# LIGHT.net
KiCad netlist of a schematic drawn in Altium Designer
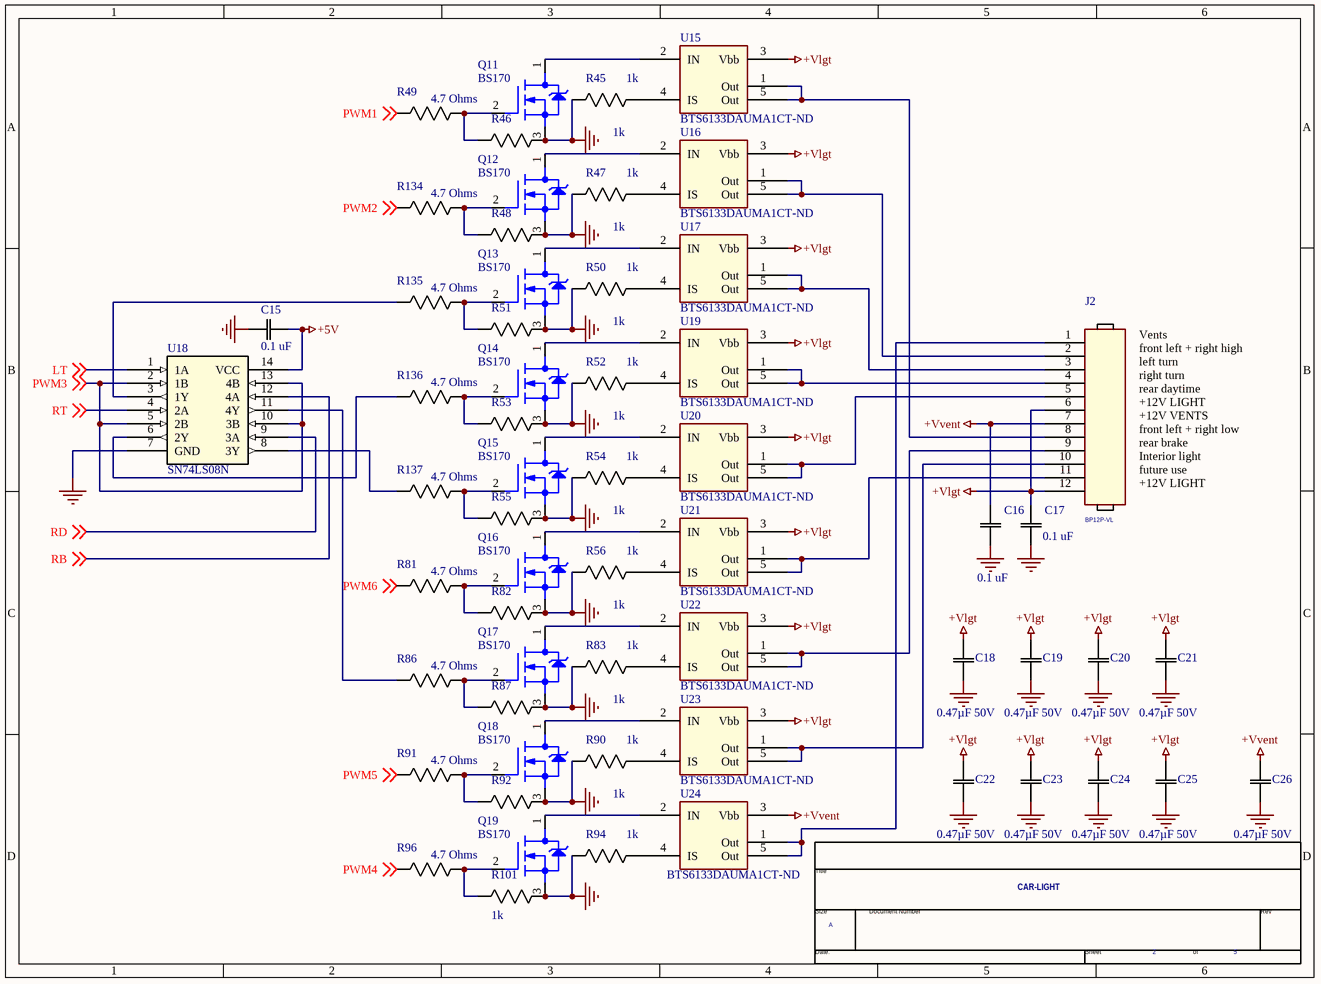
[diagram p0: LIGHT.SchDoc]

(export (version "E")
  (design (tool "Eeschema 10.0.6"))
  (components
    (comp (ref "C15")
      (value "0.1 uF")
      (footprint "SR20")
      (description "0.1µF ±10% 100V Ceramic Capacitor X7R Radial")
      (fields (field (name "MANUFACTURER_PART_NUMBER") "C320C104K1R5TA7301"))
      (libsource (lib "Discrete") (part "CAP RADIAL 2.54"))
    )
    (comp (ref "C16")
      (value "0.1 uF")
      (footprint "SR20")
      (description "0.1µF ±10% 100V Ceramic Capacitor X7R Radial")
      (fields (field (name "MANUFACTURER_PART_NUMBER") "C320C104K1R5TA7301"))
      (libsource (lib "Discrete") (part "CAP RADIAL 2.54"))
    )
    (comp (ref "C17")
      (value "0.1 uF")
      (footprint "SR20")
      (description "0.1µF ±10% 100V Ceramic Capacitor X7R Radial")
      (fields (field (name "MANUFACTURER_PART_NUMBER") "C320C104K1R5TA7301"))
      (libsource (lib "Discrete") (part "CAP RADIAL 2.54"))
    )
    (comp (ref "C18")
      (value "0.47µF 50V")
      (footprint "SR20")
      (description "CAP CER 0.47UF 50V X7R RADIAL")
      (fields (field (name "MANUFACTURER_PART_NUMBER") "C315C474K5R5TA7303"))
      (libsource (lib "Discrete") (part "CAP RADIAL 2.54"))
    )
    (comp (ref "C19")
      (value "0.47µF 50V")
      (footprint "SR20")
      (description "CAP CER 0.47UF 50V X7R RADIAL")
      (fields (field (name "MANUFACTURER_PART_NUMBER") "C315C474K5R5TA7303"))
      (libsource (lib "Discrete") (part "CAP RADIAL 2.54"))
    )
    (comp (ref "C20")
      (value "0.47µF 50V")
      (footprint "SR20")
      (description "CAP CER 0.47UF 50V X7R RADIAL")
      (fields (field (name "MANUFACTURER_PART_NUMBER") "C315C474K5R5TA7303"))
      (libsource (lib "Discrete") (part "CAP RADIAL 2.54"))
    )
    (comp (ref "C21")
      (value "0.47µF 50V")
      (footprint "SR20")
      (description "CAP CER 0.47UF 50V X7R RADIAL")
      (fields (field (name "MANUFACTURER_PART_NUMBER") "C315C474K5R5TA7303"))
      (libsource (lib "Discrete") (part "CAP RADIAL 2.54"))
    )
    (comp (ref "C22")
      (value "0.47µF 50V")
      (footprint "SR20")
      (description "CAP CER 0.47UF 50V X7R RADIAL")
      (fields (field (name "MANUFACTURER_PART_NUMBER") "C315C474K5R5TA7303"))
      (libsource (lib "Discrete") (part "CAP RADIAL 2.54"))
    )
    (comp (ref "C23")
      (value "0.47µF 50V")
      (footprint "SR20")
      (description "CAP CER 0.47UF 50V X7R RADIAL")
      (fields (field (name "MANUFACTURER_PART_NUMBER") "C315C474K5R5TA7303"))
      (libsource (lib "Discrete") (part "CAP RADIAL 2.54"))
    )
    (comp (ref "C24")
      (value "0.47µF 50V")
      (footprint "SR20")
      (description "CAP CER 0.47UF 50V X7R RADIAL")
      (fields (field (name "MANUFACTURER_PART_NUMBER") "C315C474K5R5TA7303"))
      (libsource (lib "Discrete") (part "CAP RADIAL 2.54"))
    )
    (comp (ref "C25")
      (value "0.47µF 50V")
      (footprint "SR20")
      (description "CAP CER 0.47UF 50V X7R RADIAL")
      (fields (field (name "MANUFACTURER_PART_NUMBER") "C315C474K5R5TA7303"))
      (libsource (lib "Discrete") (part "CAP RADIAL 2.54"))
    )
    (comp (ref "C26")
      (value "0.47µF 50V")
      (footprint "SR20")
      (description "CAP CER 0.47UF 50V X7R RADIAL")
      (fields (field (name "MANUFACTURER_PART_NUMBER") "C315C474K5R5TA7303"))
      (libsource (lib "Discrete") (part "CAP RADIAL 2.54"))
    )
    (comp (ref "J2")
      (value "BP12P-VL")
      (footprint "MOLEX_0874271202")
      (libsource (lib "*") (part "HEADER 12"))
    )
    (comp (ref "Q11")
      (value "BS170")
      (footprint "Discrete:TO-92")
      (description "MOSFET N-CH 60V 500MA TO-92")
      (fields (field (name "MANUFACTURER_PART_NUMBER") "ON Semiconductor"))
      (libsource (lib "Discrete") (part "BS170"))
    )
    (comp (ref "Q12")
      (value "BS170")
      (footprint "Discrete:TO-92")
      (description "MOSFET N-CH 60V 500MA TO-92")
      (fields (field (name "MANUFACTURER_PART_NUMBER") "ON Semiconductor"))
      (libsource (lib "Discrete") (part "BS170"))
    )
    (comp (ref "Q13")
      (value "BS170")
      (footprint "Discrete:TO-92")
      (description "MOSFET N-CH 60V 500MA TO-92")
      (fields (field (name "MANUFACTURER_PART_NUMBER") "ON Semiconductor"))
      (libsource (lib "Discrete") (part "BS170"))
    )
    (comp (ref "Q14")
      (value "BS170")
      (footprint "Discrete:TO-92")
      (description "MOSFET N-CH 60V 500MA TO-92")
      (fields (field (name "MANUFACTURER_PART_NUMBER") "ON Semiconductor"))
      (libsource (lib "Discrete") (part "BS170"))
    )
    (comp (ref "Q15")
      (value "BS170")
      (footprint "Discrete:TO-92")
      (description "MOSFET N-CH 60V 500MA TO-92")
      (fields (field (name "MANUFACTURER_PART_NUMBER") "ON Semiconductor"))
      (libsource (lib "Discrete") (part "BS170"))
    )
    (comp (ref "Q16")
      (value "BS170")
      (footprint "Discrete:TO-92")
      (description "MOSFET N-CH 60V 500MA TO-92")
      (fields (field (name "MANUFACTURER_PART_NUMBER") "ON Semiconductor"))
      (libsource (lib "Discrete") (part "BS170"))
    )
    (comp (ref "Q17")
      (value "BS170")
      (footprint "Discrete:TO-92")
      (description "MOSFET N-CH 60V 500MA TO-92")
      (fields (field (name "MANUFACTURER_PART_NUMBER") "ON Semiconductor"))
      (libsource (lib "Discrete") (part "BS170"))
    )
    (comp (ref "Q18")
      (value "BS170")
      (footprint "Discrete:TO-92")
      (description "MOSFET N-CH 60V 500MA TO-92")
      (fields (field (name "MANUFACTURER_PART_NUMBER") "ON Semiconductor"))
      (libsource (lib "Discrete") (part "BS170"))
    )
    (comp (ref "Q19")
      (value "BS170")
      (footprint "Discrete:TO-92")
      (description "MOSFET N-CH 60V 500MA TO-92")
      (fields (field (name "MANUFACTURER_PART_NUMBER") "ON Semiconductor"))
      (libsource (lib "Discrete") (part "BS170"))
    )
    (comp (ref "R45")
      (value "1k")
      (footprint "RES AXIAL 1/6W")
      (description "RES 1K OHM 1/6W 5% AXIAL")
      (fields (field (name "MANUFACTURER_PART_NUMBER") "CFR-12JB-52-1K"))
      (libsource (lib "Discrete") (part "Resistor Axial  1/6W"))
    )
    (comp (ref "R46")
      (value "1k")
      (footprint "RES AXIAL 1/6W")
      (description "RES 1K OHM 1/6W 5% AXIAL")
      (fields (field (name "MANUFACTURER_PART_NUMBER") "CFR-12JB-52-1K"))
      (libsource (lib "Discrete") (part "Resistor Axial  1/6W"))
    )
    (comp (ref "R47")
      (value "1k")
      (footprint "RES AXIAL 1/6W")
      (description "RES 1K OHM 1/6W 5% AXIAL")
      (fields (field (name "MANUFACTURER_PART_NUMBER") "CFR-12JB-52-1K"))
      (libsource (lib "Discrete") (part "Resistor Axial  1/6W"))
    )
    (comp (ref "R48")
      (value "1k")
      (footprint "RES AXIAL 1/6W")
      (description "RES 1K OHM 1/6W 5% AXIAL")
      (fields (field (name "MANUFACTURER_PART_NUMBER") "CFR-12JB-52-1K"))
      (libsource (lib "Discrete") (part "Resistor Axial  1/6W"))
    )
    (comp (ref "R49")
      (value "4.7 Ohms")
      (footprint "RES AXIAL 1/6W")
      (description "RES 4.7 OHM 1/6W 5% AXIAL")
      (fields (field (name "MANUFACTURER_PART_NUMBER") "CFR-12JB-52-4R7"))
      (libsource (lib "Discrete") (part "Resistor Axial  1/6W"))
    )
    (comp (ref "R50")
      (value "1k")
      (footprint "RES AXIAL 1/6W")
      (description "RES 1K OHM 1/6W 5% AXIAL")
      (fields (field (name "MANUFACTURER_PART_NUMBER") "CFR-12JB-52-1K"))
      (libsource (lib "Discrete") (part "Resistor Axial  1/6W"))
    )
    (comp (ref "R51")
      (value "1k")
      (footprint "RES AXIAL 1/6W")
      (description "RES 1K OHM 1/6W 5% AXIAL")
      (fields (field (name "MANUFACTURER_PART_NUMBER") "CFR-12JB-52-1K"))
      (libsource (lib "Discrete") (part "Resistor Axial  1/6W"))
    )
    (comp (ref "R52")
      (value "1k")
      (footprint "RES AXIAL 1/6W")
      (description "RES 1K OHM 1/6W 5% AXIAL")
      (fields (field (name "MANUFACTURER_PART_NUMBER") "CFR-12JB-52-1K"))
      (libsource (lib "Discrete") (part "Resistor Axial  1/6W"))
    )
    (comp (ref "R53")
      (value "1k")
      (footprint "RES AXIAL 1/6W")
      (description "RES 1K OHM 1/6W 5% AXIAL")
      (fields (field (name "MANUFACTURER_PART_NUMBER") "CFR-12JB-52-1K"))
      (libsource (lib "Discrete") (part "Resistor Axial  1/6W"))
    )
    (comp (ref "R54")
      (value "1k")
      (footprint "RES AXIAL 1/6W")
      (description "RES 1K OHM 1/6W 5% AXIAL")
      (fields (field (name "MANUFACTURER_PART_NUMBER") "CFR-12JB-52-1K"))
      (libsource (lib "Discrete") (part "Resistor Axial  1/6W"))
    )
    (comp (ref "R55")
      (value "1k")
      (footprint "RES AXIAL 1/6W")
      (description "RES 1K OHM 1/6W 5% AXIAL")
      (fields (field (name "MANUFACTURER_PART_NUMBER") "CFR-12JB-52-1K"))
      (libsource (lib "Discrete") (part "Resistor Axial  1/6W"))
    )
    (comp (ref "R56")
      (value "1k")
      (footprint "RES AXIAL 1/6W")
      (description "RES 1K OHM 1/6W 5% AXIAL")
      (fields (field (name "MANUFACTURER_PART_NUMBER") "CFR-12JB-52-1K"))
      (libsource (lib "Discrete") (part "Resistor Axial  1/6W"))
    )
    (comp (ref "R81")
      (value "4.7 Ohms")
      (footprint "RES AXIAL 1/6W")
      (description "RES 4.7 OHM 1/6W 5% AXIAL")
      (fields (field (name "MANUFACTURER_PART_NUMBER") "CFR-12JB-52-4R7"))
      (libsource (lib "Discrete") (part "Resistor Axial  1/6W"))
    )
    (comp (ref "R82")
      (value "1k")
      (footprint "RES AXIAL 1/6W")
      (description "RES 1K OHM 1/6W 5% AXIAL")
      (fields (field (name "MANUFACTURER_PART_NUMBER") "CFR-12JB-52-1K"))
      (libsource (lib "Discrete") (part "Resistor Axial  1/6W"))
    )
    (comp (ref "R83")
      (value "1k")
      (footprint "RES AXIAL 1/6W")
      (description "RES 1K OHM 1/6W 5% AXIAL")
      (fields (field (name "MANUFACTURER_PART_NUMBER") "CFR-12JB-52-1K"))
      (libsource (lib "Discrete") (part "Resistor Axial  1/6W"))
    )
    (comp (ref "R86")
      (value "4.7 Ohms")
      (footprint "RES AXIAL 1/6W")
      (description "RES 4.7 OHM 1/6W 5% AXIAL")
      (fields (field (name "MANUFACTURER_PART_NUMBER") "CFR-12JB-52-4R7"))
      (libsource (lib "Discrete") (part "Resistor Axial  1/6W"))
    )
    (comp (ref "R87")
      (value "1k")
      (footprint "RES AXIAL 1/6W")
      (description "RES 1K OHM 1/6W 5% AXIAL")
      (fields (field (name "MANUFACTURER_PART_NUMBER") "CFR-12JB-52-1K"))
      (libsource (lib "Discrete") (part "Resistor Axial  1/6W"))
    )
    (comp (ref "R90")
      (value "1k")
      (footprint "RES AXIAL 1/6W")
      (description "RES 1K OHM 1/6W 5% AXIAL")
      (fields (field (name "MANUFACTURER_PART_NUMBER") "CFR-12JB-52-1K"))
      (libsource (lib "Discrete") (part "Resistor Axial  1/6W"))
    )
    (comp (ref "R91")
      (value "4.7 Ohms")
      (footprint "RES AXIAL 1/6W")
      (description "RES 4.7 OHM 1/6W 5% AXIAL")
      (fields (field (name "MANUFACTURER_PART_NUMBER") "CFR-12JB-52-4R7"))
      (libsource (lib "Discrete") (part "Resistor Axial  1/6W"))
    )
    (comp (ref "R92")
      (value "1k")
      (footprint "RES AXIAL 1/6W")
      (description "RES 1K OHM 1/6W 5% AXIAL")
      (fields (field (name "MANUFACTURER_PART_NUMBER") "CFR-12JB-52-1K"))
      (libsource (lib "Discrete") (part "Resistor Axial  1/6W"))
    )
    (comp (ref "R94")
      (value "1k")
      (footprint "RES AXIAL 1/6W")
      (description "RES 1K OHM 1/6W 5% AXIAL")
      (fields (field (name "MANUFACTURER_PART_NUMBER") "CFR-12JB-52-1K"))
      (libsource (lib "Discrete") (part "Resistor Axial  1/6W"))
    )
    (comp (ref "R96")
      (value "4.7 Ohms")
      (footprint "RES AXIAL 1/6W")
      (description "RES 4.7 OHM 1/6W 5% AXIAL")
      (fields (field (name "MANUFACTURER_PART_NUMBER") "CFR-12JB-52-4R7"))
      (libsource (lib "Discrete") (part "Resistor Axial  1/6W"))
    )
    (comp (ref "R101")
      (value "1k")
      (footprint "RES AXIAL 1/6W")
      (description "RES 1K OHM 1/6W 5% AXIAL")
      (fields (field (name "MANUFACTURER_PART_NUMBER") "CFR-12JB-52-1K"))
      (libsource (lib "Discrete") (part "Resistor Axial  1/6W"))
    )
    (comp (ref "R134")
      (value "4.7 Ohms")
      (footprint "RES AXIAL 1/6W")
      (description "RES 4.7 OHM 1/6W 5% AXIAL")
      (fields (field (name "MANUFACTURER_PART_NUMBER") "CFR-12JB-52-4R7"))
      (libsource (lib "Discrete") (part "Resistor Axial  1/6W"))
    )
    (comp (ref "R135")
      (value "4.7 Ohms")
      (footprint "RES AXIAL 1/6W")
      (description "RES 4.7 OHM 1/6W 5% AXIAL")
      (fields (field (name "MANUFACTURER_PART_NUMBER") "CFR-12JB-52-4R7"))
      (libsource (lib "Discrete") (part "Resistor Axial  1/6W"))
    )
    (comp (ref "R136")
      (value "4.7 Ohms")
      (footprint "RES AXIAL 1/6W")
      (description "RES 4.7 OHM 1/6W 5% AXIAL")
      (fields (field (name "MANUFACTURER_PART_NUMBER") "CFR-12JB-52-4R7"))
      (libsource (lib "Discrete") (part "Resistor Axial  1/6W"))
    )
    (comp (ref "R137")
      (value "4.7 Ohms")
      (footprint "RES AXIAL 1/6W")
      (description "RES 4.7 OHM 1/6W 5% AXIAL")
      (fields (field (name "MANUFACTURER_PART_NUMBER") "CFR-12JB-52-4R7"))
      (libsource (lib "Discrete") (part "Resistor Axial  1/6W"))
    )
    (comp (ref "U15")
      (value "BTS6133DAUMA1CT-ND")
      (footprint "TO114P998X235-6_5N_L")
      (libsource (lib "CAR_Library") (part "BTS6133DAUMA1CT-ND"))
    )
    (comp (ref "U16")
      (value "BTS6133DAUMA1CT-ND")
      (footprint "TO114P998X235-6_5N_L")
      (libsource (lib "CAR_Library") (part "BTS6133DAUMA1CT-ND"))
    )
    (comp (ref "U17")
      (value "BTS6133DAUMA1CT-ND")
      (footprint "TO114P998X235-6_5N_L")
      (libsource (lib "CAR_Library") (part "BTS6133DAUMA1CT-ND"))
    )
    (comp (ref "U18")
      (value "SN74LS08N")
      (footprint "PDIP14_300MC")
      (description "IC GATE AND 4CH 2-INP 14DIP")
      (libsource (lib "ICs") (part "SN74LS08N"))
    )
    (comp (ref "U19")
      (value "BTS6133DAUMA1CT-ND")
      (footprint "TO114P998X235-6_5N_L")
      (libsource (lib "CAR_Library") (part "BTS6133DAUMA1CT-ND"))
    )
    (comp (ref "U20")
      (value "BTS6133DAUMA1CT-ND")
      (footprint "TO114P998X235-6_5N_L")
      (libsource (lib "CAR_Library") (part "BTS6133DAUMA1CT-ND"))
    )
    (comp (ref "U21")
      (value "BTS6133DAUMA1CT-ND")
      (footprint "TO114P998X235-6_5N_L")
      (libsource (lib "CAR_Library") (part "BTS6133DAUMA1CT-ND"))
    )
    (comp (ref "U22")
      (value "BTS6133DAUMA1CT-ND")
      (footprint "TO114P998X235-6_5N_L")
      (libsource (lib "CAR_Library") (part "BTS6133DAUMA1CT-ND"))
    )
    (comp (ref "U23")
      (value "BTS6133DAUMA1CT-ND")
      (footprint "TO114P998X235-6_5N_L")
      (libsource (lib "CAR_Library") (part "BTS6133DAUMA1CT-ND"))
    )
    (comp (ref "U24")
      (value "BTS6133DAUMA1CT-ND")
      (footprint "TO114P998X235-6_5N_L")
      (libsource (lib "CAR_Library") (part "BTS6133DAUMA1CT-ND"))
    )
  )
  (nets
    (net (code "1") (name "+5V") (class "Default")
      (node (ref "C15") (pin "1") (pinfunction "1_1") (pintype "passive"))
      (node (ref "U18") (pin "14") (pinfunction "VCC_14") (pintype "power_in"))
    )
    (net (code "2") (name "+Vlgt") (class "Default")
      (node (ref "C17") (pin "2") (pinfunction "2_2") (pintype "passive"))
      (node (ref "C18") (pin "2") (pinfunction "2_2") (pintype "passive"))
      (node (ref "C19") (pin "2") (pinfunction "2_2") (pintype "passive"))
      (node (ref "C20") (pin "2") (pinfunction "2_2") (pintype "passive"))
      (node (ref "C21") (pin "2") (pinfunction "2_2") (pintype "passive"))
      (node (ref "C22") (pin "2") (pinfunction "2_2") (pintype "passive"))
      (node (ref "C23") (pin "2") (pinfunction "2_2") (pintype "passive"))
      (node (ref "C24") (pin "2") (pinfunction "2_2") (pintype "passive"))
      (node (ref "C25") (pin "2") (pinfunction "2_2") (pintype "passive"))
      (node (ref "J2") (pin "12") (pinfunction "12_12") (pintype "passive"))
      (node (ref "J2") (pin "6") (pinfunction "6_6") (pintype "passive"))
      (node (ref "U15") (pin "3") (pinfunction "Vbb_3") (pintype "passive"))
      (node (ref "U16") (pin "3") (pinfunction "Vbb_3") (pintype "passive"))
      (node (ref "U17") (pin "3") (pinfunction "Vbb_3") (pintype "passive"))
      (node (ref "U19") (pin "3") (pinfunction "Vbb_3") (pintype "passive"))
      (node (ref "U20") (pin "3") (pinfunction "Vbb_3") (pintype "passive"))
      (node (ref "U21") (pin "3") (pinfunction "Vbb_3") (pintype "passive"))
      (node (ref "U22") (pin "3") (pinfunction "Vbb_3") (pintype "passive"))
      (node (ref "U23") (pin "3") (pinfunction "Vbb_3") (pintype "passive"))
    )
    (net (code "3") (name "+Vvent") (class "Default")
      (node (ref "C16") (pin "2") (pinfunction "2_2") (pintype "passive"))
      (node (ref "C26") (pin "2") (pinfunction "2_2") (pintype "passive"))
      (node (ref "J2") (pin "7") (pinfunction "7_7") (pintype "passive"))
      (node (ref "U24") (pin "3") (pinfunction "Vbb_3") (pintype "passive"))
    )
    (net (code "4") (name "GND") (class "Default")
      (node (ref "C15") (pin "2") (pinfunction "2_2") (pintype "passive"))
      (node (ref "C16") (pin "1") (pinfunction "1_1") (pintype "passive"))
      (node (ref "C17") (pin "1") (pinfunction "1_1") (pintype "passive"))
      (node (ref "C18") (pin "1") (pinfunction "1_1") (pintype "passive"))
      (node (ref "C19") (pin "1") (pinfunction "1_1") (pintype "passive"))
      (node (ref "C20") (pin "1") (pinfunction "1_1") (pintype "passive"))
      (node (ref "C21") (pin "1") (pinfunction "1_1") (pintype "passive"))
      (node (ref "C22") (pin "1") (pinfunction "1_1") (pintype "passive"))
      (node (ref "C23") (pin "1") (pinfunction "1_1") (pintype "passive"))
      (node (ref "C24") (pin "1") (pinfunction "1_1") (pintype "passive"))
      (node (ref "C25") (pin "1") (pinfunction "1_1") (pintype "passive"))
      (node (ref "C26") (pin "1") (pinfunction "1_1") (pintype "passive"))
      (node (ref "Q11") (pin "3") (pinfunction "S_3") (pintype "passive"))
      (node (ref "Q12") (pin "3") (pinfunction "S_3") (pintype "passive"))
      (node (ref "Q13") (pin "3") (pinfunction "S_3") (pintype "passive"))
      (node (ref "Q14") (pin "3") (pinfunction "S_3") (pintype "passive"))
      (node (ref "Q15") (pin "3") (pinfunction "S_3") (pintype "passive"))
      (node (ref "Q16") (pin "3") (pinfunction "S_3") (pintype "passive"))
      (node (ref "Q17") (pin "3") (pinfunction "S_3") (pintype "passive"))
      (node (ref "Q18") (pin "3") (pinfunction "S_3") (pintype "passive"))
      (node (ref "Q19") (pin "3") (pinfunction "S_3") (pintype "passive"))
      (node (ref "R101") (pin "1") (pinfunction "1_1") (pintype "passive"))
      (node (ref "R45") (pin "2") (pinfunction "2_2") (pintype "passive"))
      (node (ref "R46") (pin "1") (pinfunction "1_1") (pintype "passive"))
      (node (ref "R47") (pin "2") (pinfunction "2_2") (pintype "passive"))
      (node (ref "R48") (pin "1") (pinfunction "1_1") (pintype "passive"))
      (node (ref "R50") (pin "2") (pinfunction "2_2") (pintype "passive"))
      (node (ref "R51") (pin "1") (pinfunction "1_1") (pintype "passive"))
      (node (ref "R52") (pin "2") (pinfunction "2_2") (pintype "passive"))
      (node (ref "R53") (pin "1") (pinfunction "1_1") (pintype "passive"))
      (node (ref "R54") (pin "2") (pinfunction "2_2") (pintype "passive"))
      (node (ref "R55") (pin "1") (pinfunction "1_1") (pintype "passive"))
      (node (ref "R56") (pin "2") (pinfunction "2_2") (pintype "passive"))
      (node (ref "R82") (pin "1") (pinfunction "1_1") (pintype "passive"))
      (node (ref "R83") (pin "2") (pinfunction "2_2") (pintype "passive"))
      (node (ref "R87") (pin "1") (pinfunction "1_1") (pintype "passive"))
      (node (ref "R90") (pin "2") (pinfunction "2_2") (pintype "passive"))
      (node (ref "R92") (pin "1") (pinfunction "1_1") (pintype "passive"))
      (node (ref "R94") (pin "2") (pinfunction "2_2") (pintype "passive"))
      (node (ref "U18") (pin "7") (pinfunction "GND_7") (pintype "power_in"))
    )
    (net (code "5") (name "LT") (class "Default")
      (node (ref "U18") (pin "1") (pinfunction "1A_1") (pintype "input"))
    )
    (net (code "6") (name "Net-(J2-Pad1)") (class "Default")
      (node (ref "J2") (pin "1") (pinfunction "1_1") (pintype "passive"))
      (node (ref "U24") (pin "1") (pinfunction "Out_1") (pintype "passive"))
      (node (ref "U24") (pin "5") (pinfunction "Out_5") (pintype "passive"))
    )
    (net (code "7") (name "Net-(J2-Pad2)") (class "Default")
      (node (ref "J2") (pin "2") (pinfunction "2_2") (pintype "passive"))
      (node (ref "U16") (pin "1") (pinfunction "Out_1") (pintype "passive"))
      (node (ref "U16") (pin "5") (pinfunction "Out_5") (pintype "passive"))
    )
    (net (code "8") (name "Net-(J2-Pad3)") (class "Default")
      (node (ref "J2") (pin "3") (pinfunction "3_3") (pintype "passive"))
      (node (ref "U17") (pin "1") (pinfunction "Out_1") (pintype "passive"))
      (node (ref "U17") (pin "5") (pinfunction "Out_5") (pintype "passive"))
    )
    (net (code "9") (name "Net-(J2-Pad4)") (class "Default")
      (node (ref "J2") (pin "4") (pinfunction "4_4") (pintype "passive"))
      (node (ref "U19") (pin "1") (pinfunction "Out_1") (pintype "passive"))
      (node (ref "U19") (pin "5") (pinfunction "Out_5") (pintype "passive"))
    )
    (net (code "10") (name "Net-(J2-Pad5)") (class "Default")
      (node (ref "J2") (pin "5") (pinfunction "5_5") (pintype "passive"))
      (node (ref "U20") (pin "1") (pinfunction "Out_1") (pintype "passive"))
      (node (ref "U20") (pin "5") (pinfunction "Out_5") (pintype "passive"))
    )
    (net (code "11") (name "Net-(J2-Pad8)") (class "Default")
      (node (ref "J2") (pin "8") (pinfunction "8_8") (pintype "passive"))
      (node (ref "U15") (pin "1") (pinfunction "Out_1") (pintype "passive"))
      (node (ref "U15") (pin "5") (pinfunction "Out_5") (pintype "passive"))
    )
    (net (code "12") (name "Net-(J2-Pad9)") (class "Default")
      (node (ref "J2") (pin "9") (pinfunction "9_9") (pintype "passive"))
      (node (ref "U22") (pin "1") (pinfunction "Out_1") (pintype "passive"))
      (node (ref "U22") (pin "5") (pinfunction "Out_5") (pintype "passive"))
    )
    (net (code "13") (name "Net-(J2-Pad10)") (class "Default")
      (node (ref "J2") (pin "10") (pinfunction "10_10") (pintype "passive"))
      (node (ref "U23") (pin "1") (pinfunction "Out_1") (pintype "passive"))
      (node (ref "U23") (pin "5") (pinfunction "Out_5") (pintype "passive"))
    )
    (net (code "14") (name "Net-(J2-Pad11)") (class "Default")
      (node (ref "J2") (pin "11") (pinfunction "11_11") (pintype "passive"))
      (node (ref "U21") (pin "1") (pinfunction "Out_1") (pintype "passive"))
      (node (ref "U21") (pin "5") (pinfunction "Out_5") (pintype "passive"))
    )
    (net (code "15") (name "Net-(Q11-D)") (class "Default")
      (node (ref "Q11") (pin "1") (pinfunction "D_1") (pintype "passive"))
      (node (ref "U15") (pin "2") (pinfunction "IN_2") (pintype "passive"))
    )
    (net (code "16") (name "Net-(Q11-G)") (class "Default")
      (node (ref "Q11") (pin "2") (pinfunction "G_2") (pintype "passive"))
      (node (ref "R46") (pin "2") (pinfunction "2_2") (pintype "passive"))
      (node (ref "R49") (pin "1") (pinfunction "1_1") (pintype "passive"))
    )
    (net (code "17") (name "Net-(Q12-D)") (class "Default")
      (node (ref "Q12") (pin "1") (pinfunction "D_1") (pintype "passive"))
      (node (ref "U16") (pin "2") (pinfunction "IN_2") (pintype "passive"))
    )
    (net (code "18") (name "Net-(Q12-G)") (class "Default")
      (node (ref "Q12") (pin "2") (pinfunction "G_2") (pintype "passive"))
      (node (ref "R134") (pin "1") (pinfunction "1_1") (pintype "passive"))
      (node (ref "R48") (pin "2") (pinfunction "2_2") (pintype "passive"))
    )
    (net (code "19") (name "Net-(Q13-D)") (class "Default")
      (node (ref "Q13") (pin "1") (pinfunction "D_1") (pintype "passive"))
      (node (ref "U17") (pin "2") (pinfunction "IN_2") (pintype "passive"))
    )
    (net (code "20") (name "Net-(Q13-G)") (class "Default")
      (node (ref "Q13") (pin "2") (pinfunction "G_2") (pintype "passive"))
      (node (ref "R135") (pin "1") (pinfunction "1_1") (pintype "passive"))
      (node (ref "R51") (pin "2") (pinfunction "2_2") (pintype "passive"))
    )
    (net (code "21") (name "Net-(Q14-D)") (class "Default")
      (node (ref "Q14") (pin "1") (pinfunction "D_1") (pintype "passive"))
      (node (ref "U19") (pin "2") (pinfunction "IN_2") (pintype "passive"))
    )
    (net (code "22") (name "Net-(Q14-G)") (class "Default")
      (node (ref "Q14") (pin "2") (pinfunction "G_2") (pintype "passive"))
      (node (ref "R136") (pin "1") (pinfunction "1_1") (pintype "passive"))
      (node (ref "R53") (pin "2") (pinfunction "2_2") (pintype "passive"))
    )
    (net (code "23") (name "Net-(Q15-D)") (class "Default")
      (node (ref "Q15") (pin "1") (pinfunction "D_1") (pintype "passive"))
      (node (ref "U20") (pin "2") (pinfunction "IN_2") (pintype "passive"))
    )
    (net (code "24") (name "Net-(Q15-G)") (class "Default")
      (node (ref "Q15") (pin "2") (pinfunction "G_2") (pintype "passive"))
      (node (ref "R137") (pin "1") (pinfunction "1_1") (pintype "passive"))
      (node (ref "R55") (pin "2") (pinfunction "2_2") (pintype "passive"))
    )
    (net (code "25") (name "Net-(Q16-D)") (class "Default")
      (node (ref "Q16") (pin "1") (pinfunction "D_1") (pintype "passive"))
      (node (ref "U21") (pin "2") (pinfunction "IN_2") (pintype "passive"))
    )
    (net (code "26") (name "Net-(Q16-G)") (class "Default")
      (node (ref "Q16") (pin "2") (pinfunction "G_2") (pintype "passive"))
      (node (ref "R81") (pin "1") (pinfunction "1_1") (pintype "passive"))
      (node (ref "R82") (pin "2") (pinfunction "2_2") (pintype "passive"))
    )
    (net (code "27") (name "Net-(Q17-D)") (class "Default")
      (node (ref "Q17") (pin "1") (pinfunction "D_1") (pintype "passive"))
      (node (ref "U22") (pin "2") (pinfunction "IN_2") (pintype "passive"))
    )
    (net (code "28") (name "Net-(Q17-G)") (class "Default")
      (node (ref "Q17") (pin "2") (pinfunction "G_2") (pintype "passive"))
      (node (ref "R86") (pin "1") (pinfunction "1_1") (pintype "passive"))
      (node (ref "R87") (pin "2") (pinfunction "2_2") (pintype "passive"))
    )
    (net (code "29") (name "Net-(Q18-D)") (class "Default")
      (node (ref "Q18") (pin "1") (pinfunction "D_1") (pintype "passive"))
      (node (ref "U23") (pin "2") (pinfunction "IN_2") (pintype "passive"))
    )
    (net (code "30") (name "Net-(Q18-G)") (class "Default")
      (node (ref "Q18") (pin "2") (pinfunction "G_2") (pintype "passive"))
      (node (ref "R91") (pin "1") (pinfunction "1_1") (pintype "passive"))
      (node (ref "R92") (pin "2") (pinfunction "2_2") (pintype "passive"))
    )
    (net (code "31") (name "Net-(Q19-D)") (class "Default")
      (node (ref "Q19") (pin "1") (pinfunction "D_1") (pintype "passive"))
      (node (ref "U24") (pin "2") (pinfunction "IN_2") (pintype "passive"))
    )
    (net (code "32") (name "Net-(Q19-G)") (class "Default")
      (node (ref "Q19") (pin "2") (pinfunction "G_2") (pintype "passive"))
      (node (ref "R101") (pin "2") (pinfunction "2_2") (pintype "passive"))
      (node (ref "R96") (pin "1") (pinfunction "1_1") (pintype "passive"))
    )
    (net (code "33") (name "Net-(U15-IS)") (class "Default")
      (node (ref "R45") (pin "1") (pinfunction "1_1") (pintype "passive"))
      (node (ref "U15") (pin "4") (pinfunction "IS_4") (pintype "passive"))
    )
    (net (code "34") (name "Net-(U16-IS)") (class "Default")
      (node (ref "R47") (pin "1") (pinfunction "1_1") (pintype "passive"))
      (node (ref "U16") (pin "4") (pinfunction "IS_4") (pintype "passive"))
    )
    (net (code "35") (name "Net-(U17-IS)") (class "Default")
      (node (ref "R50") (pin "1") (pinfunction "1_1") (pintype "passive"))
      (node (ref "U17") (pin "4") (pinfunction "IS_4") (pintype "passive"))
    )
    (net (code "36") (name "Net-(U18-1Y)") (class "Default")
      (node (ref "R135") (pin "2") (pinfunction "2_2") (pintype "passive"))
      (node (ref "U18") (pin "3") (pinfunction "1Y_3") (pintype "output"))
    )
    (net (code "37") (name "Net-(U18-2Y)") (class "Default")
      (node (ref "R136") (pin "2") (pinfunction "2_2") (pintype "passive"))
      (node (ref "U18") (pin "6") (pinfunction "2Y_6") (pintype "output"))
    )
    (net (code "38") (name "Net-(U18-3Y)") (class "Default")
      (node (ref "R137") (pin "2") (pinfunction "2_2") (pintype "passive"))
      (node (ref "U18") (pin "8") (pinfunction "3Y_8") (pintype "output"))
    )
    (net (code "39") (name "Net-(U18-4Y)") (class "Default")
      (node (ref "R86") (pin "2") (pinfunction "2_2") (pintype "passive"))
      (node (ref "U18") (pin "11") (pinfunction "4Y_11") (pintype "output"))
    )
    (net (code "40") (name "Net-(U19-IS)") (class "Default")
      (node (ref "R52") (pin "1") (pinfunction "1_1") (pintype "passive"))
      (node (ref "U19") (pin "4") (pinfunction "IS_4") (pintype "passive"))
    )
    (net (code "41") (name "Net-(U20-IS)") (class "Default")
      (node (ref "R54") (pin "1") (pinfunction "1_1") (pintype "passive"))
      (node (ref "U20") (pin "4") (pinfunction "IS_4") (pintype "passive"))
    )
    (net (code "42") (name "Net-(U21-IS)") (class "Default")
      (node (ref "R56") (pin "1") (pinfunction "1_1") (pintype "passive"))
      (node (ref "U21") (pin "4") (pinfunction "IS_4") (pintype "passive"))
    )
    (net (code "43") (name "Net-(U22-IS)") (class "Default")
      (node (ref "R83") (pin "1") (pinfunction "1_1") (pintype "passive"))
      (node (ref "U22") (pin "4") (pinfunction "IS_4") (pintype "passive"))
    )
    (net (code "44") (name "Net-(U23-IS)") (class "Default")
      (node (ref "R90") (pin "1") (pinfunction "1_1") (pintype "passive"))
      (node (ref "U23") (pin "4") (pinfunction "IS_4") (pintype "passive"))
    )
    (net (code "45") (name "Net-(U24-IS)") (class "Default")
      (node (ref "R94") (pin "1") (pinfunction "1_1") (pintype "passive"))
      (node (ref "U24") (pin "4") (pinfunction "IS_4") (pintype "passive"))
    )
    (net (code "46") (name "PWM1") (class "Default")
      (node (ref "R49") (pin "2") (pinfunction "2_2") (pintype "passive"))
    )
    (net (code "47") (name "PWM2") (class "Default")
      (node (ref "R134") (pin "2") (pinfunction "2_2") (pintype "passive"))
    )
    (net (code "48") (name "PWM3") (class "Default")
      (node (ref "U18") (pin "10") (pinfunction "3B_10") (pintype "input"))
      (node (ref "U18") (pin "13") (pinfunction "4B_13") (pintype "input"))
      (node (ref "U18") (pin "2") (pinfunction "1B_2") (pintype "input"))
      (node (ref "U18") (pin "5") (pinfunction "2B_5") (pintype "input"))
    )
    (net (code "49") (name "PWM4") (class "Default")
      (node (ref "R96") (pin "2") (pinfunction "2_2") (pintype "passive"))
    )
    (net (code "50") (name "PWM5") (class "Default")
      (node (ref "R91") (pin "2") (pinfunction "2_2") (pintype "passive"))
    )
    (net (code "51") (name "PWM6") (class "Default")
      (node (ref "R81") (pin "2") (pinfunction "2_2") (pintype "passive"))
    )
    (net (code "52") (name "RB") (class "Default")
      (node (ref "U18") (pin "12") (pinfunction "4A_12") (pintype "input"))
    )
    (net (code "53") (name "RD") (class "Default")
      (node (ref "U18") (pin "9") (pinfunction "3A_9") (pintype "input"))
    )
    (net (code "54") (name "RT") (class "Default")
      (node (ref "U18") (pin "4") (pinfunction "2A_4") (pintype "input"))
    )
  )
)
